# FRONT-UNIT-3_2.net
KiCad netlist of a schematic drawn in Altium Designer
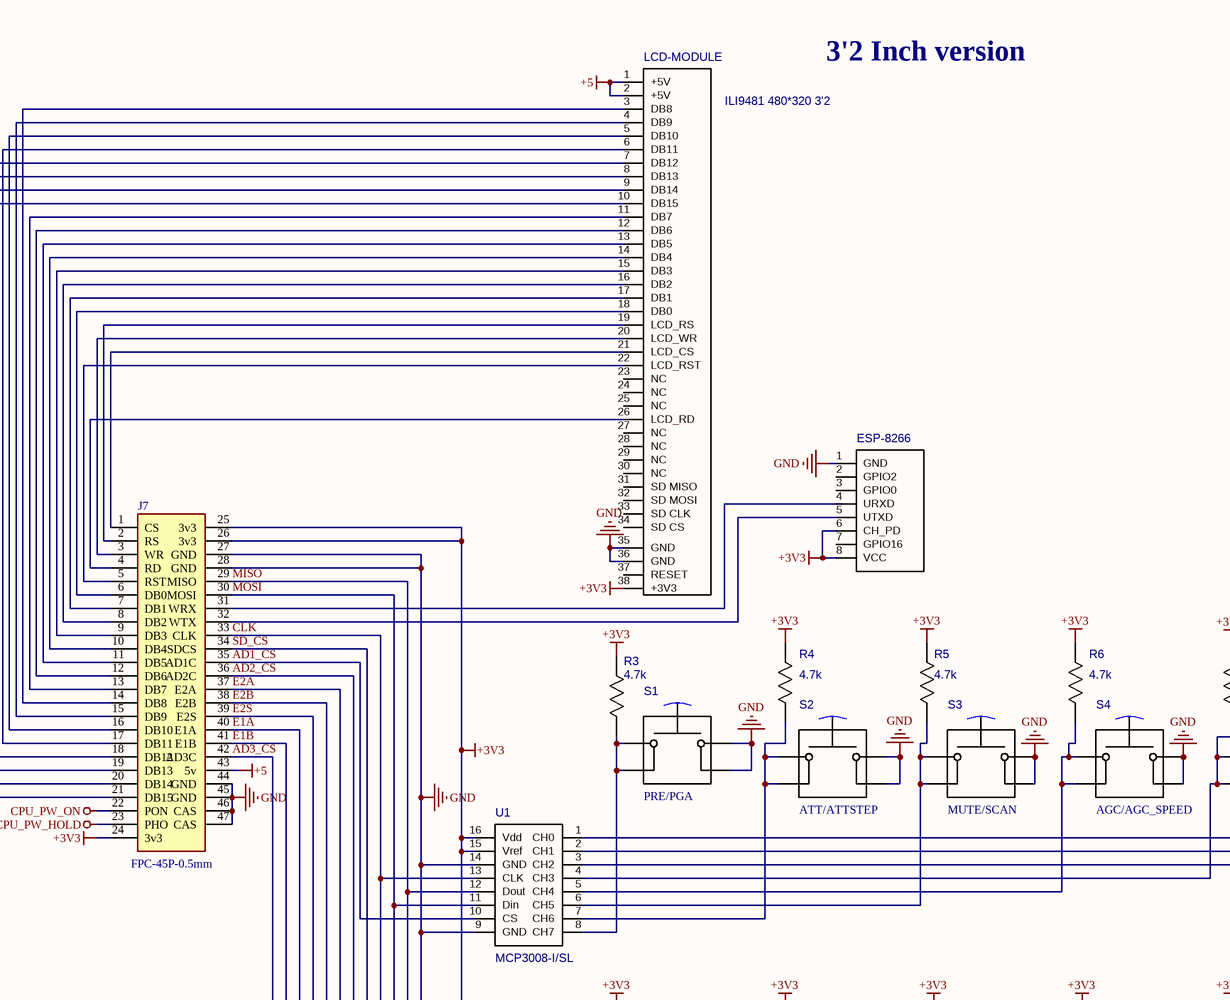
[diagram p0: FRONT-UNIT-3.2.SCHDOC, top left]
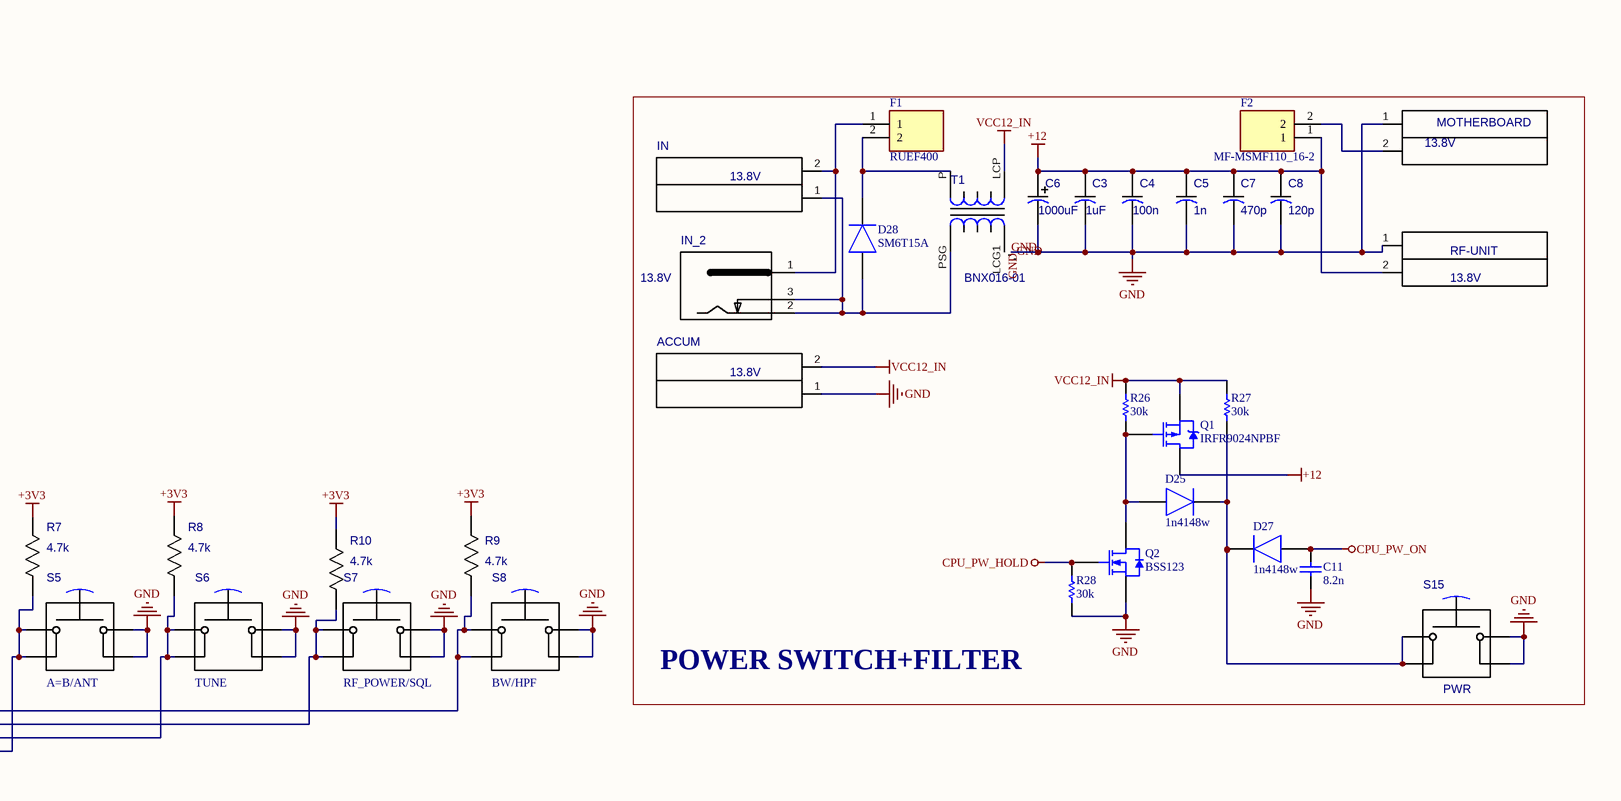
[diagram p1: FRONT-UNIT-3.2.SCHDOC, top right]
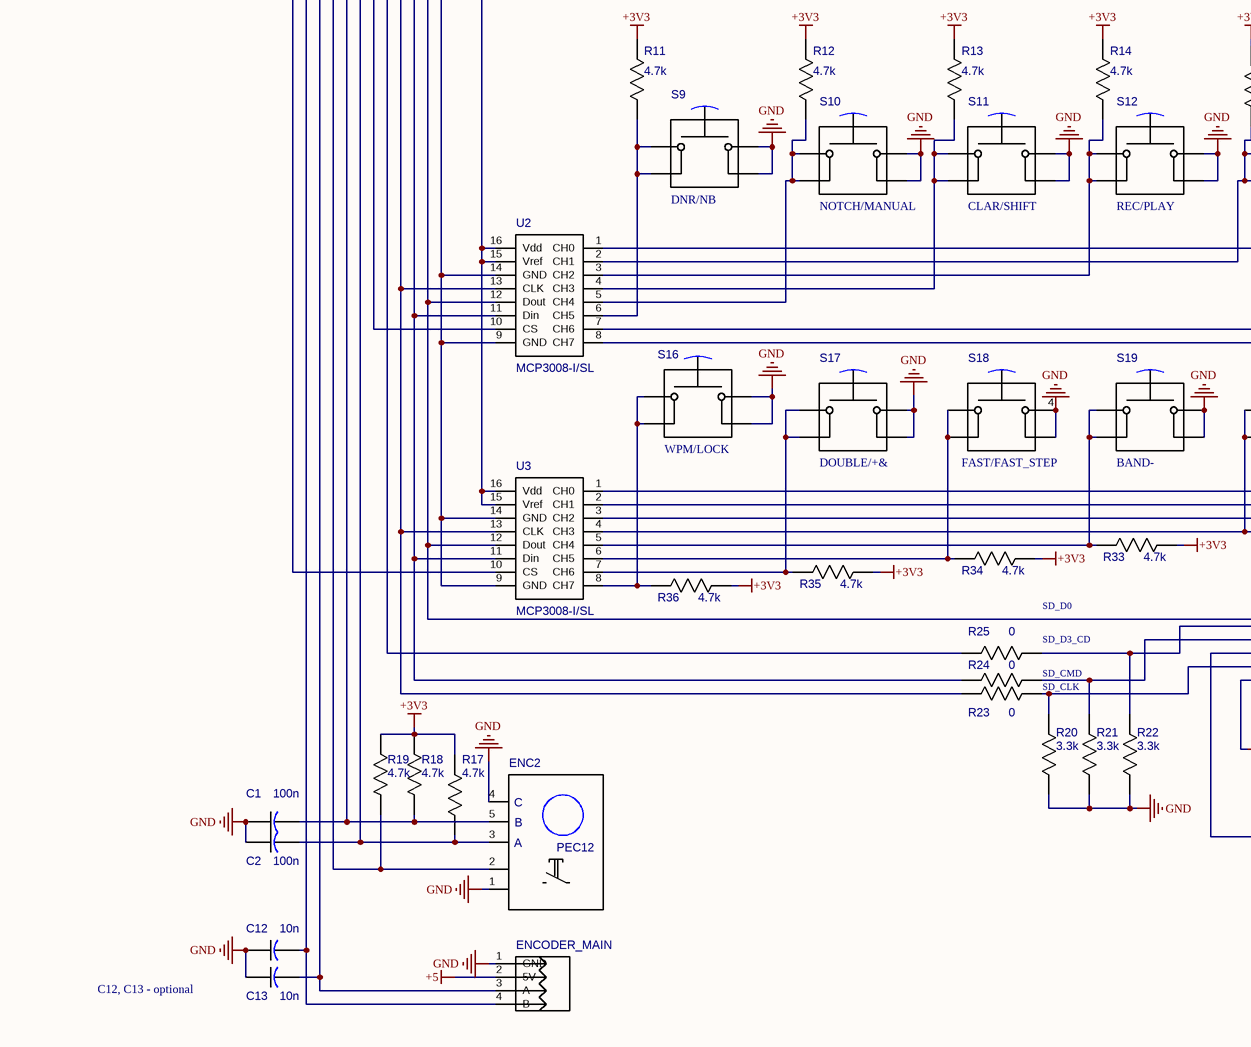
[diagram p2: FRONT-UNIT-3.2.SCHDOC, bottom left]
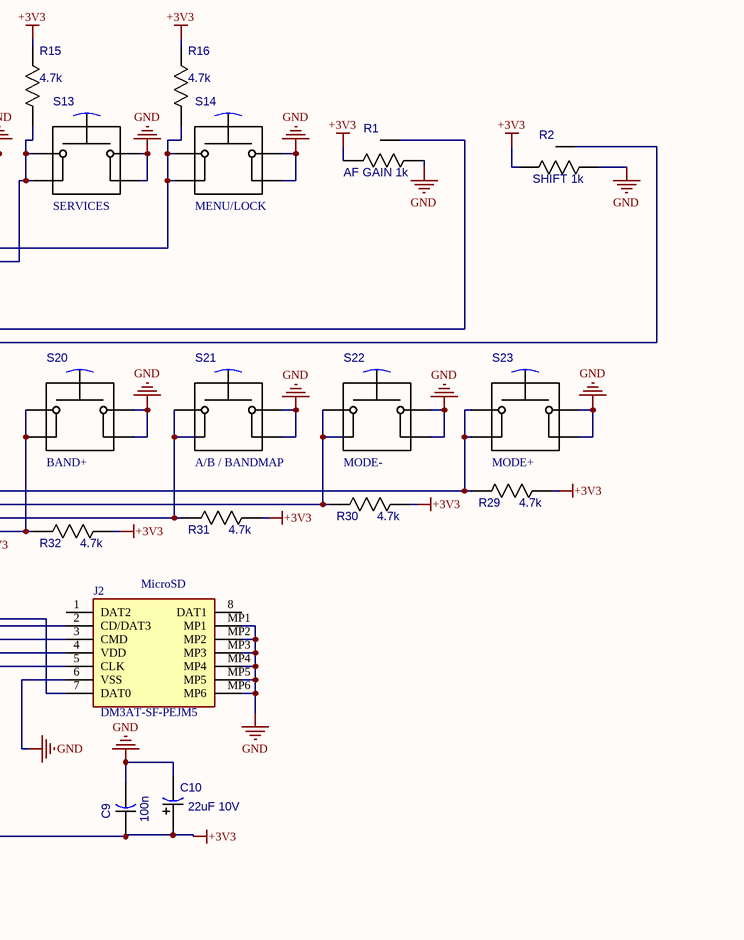
[diagram p3: FRONT-UNIT-3.2.SCHDOC, bottom right]

(export (version "E")
  (design (tool "Eeschema 10.0.6"))
  (components
    (comp (ref "ACCUM")
      (value "13.8V")
      (footprint "JX2")
      (description "JX2")
      (libsource (lib "*") (part "JX2"))
    )
    (comp (ref "C1")
      (value "100n")
      (footprint "CAP_0805")
      (description "CAP_0805")
      (libsource (lib "*") (part "CAP_0805"))
    )
    (comp (ref "C2")
      (value "100n")
      (footprint "CAP_0805")
      (description "CAP_0805")
      (libsource (lib "*") (part "CAP_0805"))
    )
    (comp (ref "C3")
      (value "1uF")
      (footprint "CAP_1206")
      (description "CAP_1206")
      (libsource (lib "*") (part "CAP_1206"))
    )
    (comp (ref "C4")
      (value "100n")
      (footprint "CAP_1206")
      (description "CAP_1206")
      (libsource (lib "*") (part "CAP_1206"))
    )
    (comp (ref "C5")
      (value "1n")
      (footprint "CAP_1206")
      (description "CAP_1206")
      (libsource (lib "*") (part "CAP_1206"))
    )
    (comp (ref "C6")
      (value "1000uF")
      (footprint "CAP250RP")
      (description "CAP250RP")
      (libsource (lib "*") (part "CAP250RP"))
    )
    (comp (ref "C7")
      (value "470p")
      (footprint "CAP_1206")
      (description "CAP_1206")
      (libsource (lib "*") (part "CAP_1206"))
    )
    (comp (ref "C8")
      (value "120p")
      (footprint "CAP_1206")
      (description "CAP_1206")
      (libsource (lib "*") (part "CAP_1206"))
    )
    (comp (ref "C9")
      (value "100n")
      (footprint "CAP_0805")
      (description "CAP_0805")
      (libsource (lib "*") (part "CAP_0805"))
    )
    (comp (ref "C10")
      (value "22uF 10V")
      (footprint "EEEFC_sizeB")
      (description "EEEFC_sizeB")
      (libsource (lib "*") (part "EEEFC_sizeB"))
    )
    (comp (ref "C11")
      (value "8.2n")
      (footprint "CAPC2013X94X50LL20T25")
      (description "CAP_1206")
      (fields
        (field (name "MANUFACTURER") "AVX Interconnect / Elco")
        (field (name "PART NUMBER") "08055C822KAT2A")
      )
      (libsource (lib "Altium Content Vault") (part "CAP"))
    )
    (comp (ref "C12")
      (value "10n")
      (footprint "CAP_0805")
      (description "CAP_0805")
      (libsource (lib "*") (part "CAP_0805"))
    )
    (comp (ref "C13")
      (value "10n")
      (footprint "CAP_0805")
      (description "CAP_0805")
      (libsource (lib "*") (part "CAP_0805"))
    )
    (comp (ref "D25")
      (value "1n4148w")
      (footprint "SamacSys:SOD3716X135N")
      (description "Diode")
      (libsource (lib "*") (part "1n4148w"))
    )
    (comp (ref "D27")
      (value "1n4148w")
      (footprint "SamacSys:SOD3716X135N")
      (description "Diode")
      (libsource (lib "*") (part "1n4148w"))
    )
    (comp (ref "D28")
      (value "SM6T15A")
      (footprint "SamacSys:SMBJ36CATR")
      (description "Diode")
      (fields (field (name "MOUSER PART NUMBER") "511-SM6T15A") (field (name "RS PART NUMBER") "4864915P"))
      (libsource (lib "*") (part "SM6T15A"))
    )
    (comp (ref "ENC2") (value "PEC12") (footprint "PEC12") (libsource (lib "*") (part "PEC12")))
    (comp (ref "ENCODER_MAIN")
      (value "OPTICAL ENCODER")
      (footprint "644456-4")
      (libsource (lib "*") (part "644456-4"))
    )
    (comp (ref "ESP-8266")
      (value "ESP-01 ESP8266")
      (footprint "ESP-01 ESP8266")
      (libsource (lib "*") (part "ESP-01 ESP8266"))
    )
    (comp (ref "F1")
      (value "RUEF400")
      (footprint "SamacSys:RUEF400")
      (description "Fuse")
      (fields (field (name "MOUSER PART NUMBER") "650-RUEF400") (field (name "RS PART NUMBER") "5176837P"))
      (libsource (lib "*") (part "RUEF400"))
    )
    (comp (ref "F2")
      (value "MF-MSMF110_16-2")
      (footprint "SamacSys:FUSC4632X85N")
      (description "Fuse")
      (fields
        (field (name "MANUFACTURER_PART_NUMBER") "MF-MSMF110/16-2")
        (field (name "MOUSER PART NUMBER") "652-MF-MSMF110/16-2")
      )
      (libsource (lib "*") (part "MF-MSMF110_16-2"))
    )
    (comp (ref "IN") (value "13.8V") (footprint "JX2") (description "JX2") (libsource (lib "*") (part "JX2")))
    (comp (ref "IN_2")
      (value "13.8V")
      (footprint "PJ-050B")
      (description "PJ-050B")
      (libsource (lib "*") (part "PJ-050B"))
    )
    (comp (ref "J2")
      (value "DM3AT-SF-PEJM5")
      (footprint "SamacSys:DM3ATSFPEJM5")
      (description "Connector")
      (libsource (lib "*") (part "DM3AT-SF-PEJM5"))
    )
    (comp (ref "J7")
      (value "FPC-45P-0.5mm")
      (footprint "FRONT-UNIT:FH12S45S05SH60")
      (description "Connector")
      (fields
        (field (name "MANUFACTURER_PART_NUMBER") "FH12S-45S-0.5SH(55)")
        (field (name "MOUSER PART NUMBER") "798-FH12S-45S-05SH55")
      )
      (libsource (lib "*") (part "FH12S-45S-0.5SH_55_"))
    )
    (comp (ref "LCD-MODULE")
      (value "ILI9481 480*320 3'2")
      (footprint "LCD-MODULE-3.2-480-320")
      (description "LCD-MODULE_3'2_480х320")
      (libsource (lib "FRONT-UNIT") (part "LCD-MODULE_3'2_480х320"))
    )
    (comp (ref "MOTHERBOARD")
      (value "13.8V")
      (footprint "JX2")
      (description "JX2")
      (libsource (lib "*") (part "JX2"))
    )
    (comp (ref "Q1")
      (value "IRFR9024NPBF")
      (footprint "ONSC-DPAK-3-369C-01_V")
      (description "IRFR9024NPBF, Транзистор, Р-канал 55В 11А")
      (fields (field (name "MANUFACTURER") "On Semiconductor") (field (name "PARTNUMBER") "NTD2955G"))
      (libsource (lib "Altium Content Vault") (part "ONSC-PMOS-G1S3D4-3_B"))
    )
    (comp (ref "Q2")
      (value "BSS123")
      (footprint "FAIR-SOT23-3_V")
      (fields (field (name "MANUFACTURER") "Fairchild"))
      (libsource (lib "Altium Content Vault") (part "NEMOS-GSD-3"))
    )
    (comp (ref "R1")
      (value "AF GAIN 1k")
      (footprint "PTV09")
      (description "Adjustable Resistor PTV09")
      (fields (field (name "Comment") "ptv09a-4225f-b102"))
      (libsource (lib "*") (part "PTV09"))
    )
    (comp (ref "R2")
      (value "SHIFT 1k")
      (footprint "PTV09")
      (description "Adjustable Resistor PTV09")
      (fields (field (name "Comment") "ptv09a-4225f-b102"))
      (libsource (lib "*") (part "PTV09"))
    )
    (comp (ref "R3")
      (value "4.7k")
      (footprint "RES_0805")
      (description "RES_0805")
      (libsource (lib "*") (part "RES_0805"))
    )
    (comp (ref "R4")
      (value "4.7k")
      (footprint "RES_0805")
      (description "RES_0805")
      (libsource (lib "*") (part "RES_0805"))
    )
    (comp (ref "R5")
      (value "4.7k")
      (footprint "RES_0805")
      (description "RES_0805")
      (libsource (lib "*") (part "RES_0805"))
    )
    (comp (ref "R6")
      (value "4.7k")
      (footprint "RES_0805")
      (description "RES_0805")
      (libsource (lib "*") (part "RES_0805"))
    )
    (comp (ref "R7")
      (value "4.7k")
      (footprint "RES_0805")
      (description "RES_0805")
      (libsource (lib "*") (part "RES_0805"))
    )
    (comp (ref "R8")
      (value "4.7k")
      (footprint "RES_0805")
      (description "RES_0805")
      (libsource (lib "*") (part "RES_0805"))
    )
    (comp (ref "R9")
      (value "4.7k")
      (footprint "RES_0805")
      (description "RES_0805")
      (libsource (lib "*") (part "RES_0805"))
    )
    (comp (ref "R10")
      (value "4.7k")
      (footprint "RES_0805")
      (description "RES_0805")
      (libsource (lib "*") (part "RES_0805"))
    )
    (comp (ref "R11")
      (value "4.7k")
      (footprint "RES_0805")
      (description "RES_0805")
      (libsource (lib "*") (part "RES_0805"))
    )
    (comp (ref "R12")
      (value "4.7k")
      (footprint "RES_0805")
      (description "RES_0805")
      (libsource (lib "*") (part "RES_0805"))
    )
    (comp (ref "R13")
      (value "4.7k")
      (footprint "RES_0805")
      (description "RES_0805")
      (libsource (lib "*") (part "RES_0805"))
    )
    (comp (ref "R14")
      (value "4.7k")
      (footprint "RES_0805")
      (description "RES_0805")
      (libsource (lib "*") (part "RES_0805"))
    )
    (comp (ref "R15")
      (value "4.7k")
      (footprint "RES_0805")
      (description "RES_0805")
      (libsource (lib "*") (part "RES_0805"))
    )
    (comp (ref "R16")
      (value "4.7k")
      (footprint "RES_0805")
      (description "RES_0805")
      (libsource (lib "*") (part "RES_0805"))
    )
    (comp (ref "R17")
      (value "4.7k")
      (footprint "RES_0805")
      (description "RES_0805")
      (libsource (lib "*") (part "RES_0805"))
    )
    (comp (ref "R18")
      (value "4.7k")
      (footprint "RES_0805")
      (description "RES_0805")
      (libsource (lib "*") (part "RES_0805"))
    )
    (comp (ref "R19")
      (value "4.7k")
      (footprint "RES_0805")
      (description "RES_0805")
      (libsource (lib "*") (part "RES_0805"))
    )
    (comp (ref "R20")
      (value "3.3k")
      (footprint "RES_0805")
      (description "RES_0805")
      (libsource (lib "*") (part "RES_0805"))
    )
    (comp (ref "R21")
      (value "3.3k")
      (footprint "RES_0805")
      (description "RES_0805")
      (libsource (lib "*") (part "RES_0805"))
    )
    (comp (ref "R22")
      (value "3.3k")
      (footprint "RES_0805")
      (description "RES_0805")
      (libsource (lib "*") (part "RES_0805"))
    )
    (comp (ref "R23")
      (value "0")
      (footprint "RES_0805")
      (description "RES_0805")
      (libsource (lib "*") (part "RES_0805"))
    )
    (comp (ref "R24")
      (value "0")
      (footprint "RES_0805")
      (description "RES_0805")
      (libsource (lib "*") (part "RES_0805"))
    )
    (comp (ref "R25")
      (value "0")
      (footprint "RES_0805")
      (description "RES_0805")
      (libsource (lib "*") (part "RES_0805"))
    )
    (comp (ref "R26")
      (value "30k")
      (footprint "RESC2013X60X40NL20T25")
      (description "RES_0805")
      (fields (field (name "MANUFACTURER") "Panasonic") (field (name "PART NUMBER") "ERA-6AEB303V"))
      (libsource (lib "Altium Content Vault") (part "RES"))
    )
    (comp (ref "R27")
      (value "30k")
      (footprint "RESC2013X60X40NL20T25")
      (description "RES_0805")
      (fields (field (name "MANUFACTURER") "Panasonic") (field (name "PART NUMBER") "ERA-6AEB303V"))
      (libsource (lib "Altium Content Vault") (part "RES"))
    )
    (comp (ref "R28")
      (value "30k")
      (footprint "RESC2013X60X40NL20T25")
      (description "RES_0805")
      (fields (field (name "MANUFACTURER") "Panasonic") (field (name "PART NUMBER") "ERA-6AEB303V"))
      (libsource (lib "Altium Content Vault") (part "RES"))
    )
    (comp (ref "R29")
      (value "4.7k")
      (footprint "RES_0805")
      (description "RES_0805")
      (libsource (lib "*") (part "RES_0805"))
    )
    (comp (ref "R30")
      (value "4.7k")
      (footprint "RES_0805")
      (description "RES_0805")
      (libsource (lib "*") (part "RES_0805"))
    )
    (comp (ref "R31")
      (value "4.7k")
      (footprint "RES_0805")
      (description "RES_0805")
      (libsource (lib "*") (part "RES_0805"))
    )
    (comp (ref "R32")
      (value "4.7k")
      (footprint "RES_0805")
      (description "RES_0805")
      (libsource (lib "*") (part "RES_0805"))
    )
    (comp (ref "R33")
      (value "4.7k")
      (footprint "RES_0805")
      (description "RES_0805")
      (libsource (lib "*") (part "RES_0805"))
    )
    (comp (ref "R34")
      (value "4.7k")
      (footprint "RES_0805")
      (description "RES_0805")
      (libsource (lib "*") (part "RES_0805"))
    )
    (comp (ref "R35")
      (value "4.7k")
      (footprint "RES_0805")
      (description "RES_0805")
      (libsource (lib "*") (part "RES_0805"))
    )
    (comp (ref "R36")
      (value "4.7k")
      (footprint "RES_0805")
      (description "RES_0805")
      (libsource (lib "*") (part "RES_0805"))
    )
    (comp (ref "RF-UNIT")
      (value "13.8V")
      (footprint "JX2")
      (description "JX2")
      (libsource (lib "*") (part "JX2"))
    )
    (comp (ref "S1")
      (value "PTS645SK50LFS")
      (footprint "PTS645SK50LFS")
      (fields (field (name "LCSC PART #") "test"))
      (libsource (lib "*") (part "PTS645SK50LFS"))
    )
    (comp (ref "S2")
      (value "PTS645SK50LFS")
      (footprint "PTS645SK50LFS")
      (libsource (lib "*") (part "PTS645SK50LFS"))
    )
    (comp (ref "S3")
      (value "PTS645SK50LFS")
      (footprint "PTS645SK50LFS")
      (libsource (lib "*") (part "PTS645SK50LFS"))
    )
    (comp (ref "S4")
      (value "PTS645SK50LFS")
      (footprint "PTS645SK50LFS")
      (libsource (lib "*") (part "PTS645SK50LFS"))
    )
    (comp (ref "S5")
      (value "PTS645SK50LFS")
      (footprint "PTS645SK50LFS")
      (libsource (lib "*") (part "PTS645SK50LFS"))
    )
    (comp (ref "S6")
      (value "PTS645SK50LFS")
      (footprint "PTS645SK50LFS")
      (libsource (lib "*") (part "PTS645SK50LFS"))
    )
    (comp (ref "S7")
      (value "PTS645SK50LFS")
      (footprint "PTS645SK50LFS")
      (libsource (lib "*") (part "PTS645SK50LFS"))
    )
    (comp (ref "S8")
      (value "PTS645SK50LFS")
      (footprint "PTS645SK50LFS")
      (libsource (lib "*") (part "PTS645SK50LFS"))
    )
    (comp (ref "S9")
      (value "PTS645SK50LFS")
      (footprint "PTS645SK50LFS")
      (libsource (lib "*") (part "PTS645SK50LFS"))
    )
    (comp (ref "S10")
      (value "PTS645SK50LFS")
      (footprint "PTS645SK50LFS")
      (libsource (lib "*") (part "PTS645SK50LFS"))
    )
    (comp (ref "S11")
      (value "PTS645SK50LFS")
      (footprint "PTS645SK50LFS")
      (libsource (lib "*") (part "PTS645SK50LFS"))
    )
    (comp (ref "S12")
      (value "PTS645SK50LFS")
      (footprint "PTS645SK50LFS")
      (libsource (lib "*") (part "PTS645SK50LFS"))
    )
    (comp (ref "S13")
      (value "PTS645SK50LFS")
      (footprint "PTS645SK50LFS")
      (libsource (lib "*") (part "PTS645SK50LFS"))
    )
    (comp (ref "S14")
      (value "PTS645SK50LFS")
      (footprint "PTS645SK50LFS")
      (libsource (lib "*") (part "PTS645SK50LFS"))
    )
    (comp (ref "S15")
      (value "PWR")
      (footprint "PTS645SK50LFS")
      (description "PTS645SK50LFS")
      (libsource (lib "*") (part "PTS645SK50LFS"))
    )
    (comp (ref "S16")
      (value "PTS645SK50LFS")
      (footprint "PTS645SK50LFS")
      (libsource (lib "*") (part "PTS645SK50LFS"))
    )
    (comp (ref "S17")
      (value "PTS645SK50LFS")
      (footprint "PTS645SK50LFS")
      (libsource (lib "*") (part "PTS645SK50LFS"))
    )
    (comp (ref "S18")
      (value "PTS645SK50LFS")
      (footprint "PTS645SK50LFS")
      (libsource (lib "") (part "PTS645SK50LFS_1"))
    )
    (comp (ref "S19")
      (value "PTS645SK50LFS")
      (footprint "PTS645SK50LFS")
      (libsource (lib "*") (part "PTS645SK50LFS"))
    )
    (comp (ref "S20")
      (value "PTS645SK50LFS")
      (footprint "PTS645SK50LFS")
      (libsource (lib "*") (part "PTS645SK50LFS"))
    )
    (comp (ref "S21")
      (value "PTS645SK50LFS")
      (footprint "PTS645SK50LFS")
      (libsource (lib "*") (part "PTS645SK50LFS"))
    )
    (comp (ref "S22")
      (value "PTS645SK50LFS")
      (footprint "PTS645SK50LFS")
      (libsource (lib "*") (part "PTS645SK50LFS"))
    )
    (comp (ref "S23")
      (value "PTS645SK50LFS")
      (footprint "PTS645SK50LFS")
      (libsource (lib "*") (part "PTS645SK50LFS"))
    )
    (comp (ref "T1")
      (value "BNX016-01")
      (footprint "TRANSF_ICORE")
      (libsource (lib "*") (part "TRANSF_ICORE"))
    )
    (comp (ref "U1")
      (value "MCP3008-I/SL")
      (footprint "MCP3008-I/SL")
      (libsource (lib "*") (part "MCP3008-I/SL"))
    )
    (comp (ref "U2")
      (value "MCP3008-I/SL")
      (footprint "MCP3008-I/SL")
      (libsource (lib "*") (part "MCP3008-I/SL"))
    )
    (comp (ref "U3")
      (value "MCP3008-I/SL")
      (footprint "MCP3008-I/SL")
      (libsource (lib "*") (part "MCP3008-I/SL"))
    )
  )
  (nets
    (net (code "1") (name "+3V3") (class "Default")
      (node (ref "C10") (pin "1") (pinfunction "PLUS_1") (pintype "passive"))
      (node (ref "C9") (pin "1") (pinfunction "1_1") (pintype "passive"))
      (node (ref "ESP-8266") (pin "6") (pinfunction "CH_PD_6") (pintype "passive"))
      (node (ref "ESP-8266") (pin "8") (pinfunction "VCC_8") (pintype "passive"))
      (node (ref "J2") (pin "4") (pinfunction "VDD_4") (pintype "passive"))
      (node (ref "J7") (pin "24") (pinfunction "3v3_24") (pintype "passive"))
      (node (ref "J7") (pin "25") (pinfunction "3v3_25") (pintype "passive"))
      (node (ref "J7") (pin "26") (pinfunction "3v3_26") (pintype "passive"))
      (node (ref "LCD-MODULE") (pin "38") (pinfunction "+3V3_38") (pintype "passive"))
      (node (ref "R1") (pin "1") (pinfunction "CW_1") (pintype "passive"))
      (node (ref "R10") (pin "2") (pinfunction "2_2") (pintype "passive"))
      (node (ref "R11") (pin "2") (pinfunction "2_2") (pintype "passive"))
      (node (ref "R12") (pin "2") (pinfunction "2_2") (pintype "passive"))
      (node (ref "R13") (pin "2") (pinfunction "2_2") (pintype "passive"))
      (node (ref "R14") (pin "2") (pinfunction "2_2") (pintype "passive"))
      (node (ref "R15") (pin "2") (pinfunction "2_2") (pintype "passive"))
      (node (ref "R16") (pin "2") (pinfunction "2_2") (pintype "passive"))
      (node (ref "R17") (pin "2") (pinfunction "2_2") (pintype "passive"))
      (node (ref "R18") (pin "2") (pinfunction "2_2") (pintype "passive"))
      (node (ref "R19") (pin "2") (pinfunction "2_2") (pintype "passive"))
      (node (ref "R2") (pin "1") (pinfunction "CW_1") (pintype "passive"))
      (node (ref "R29") (pin "2") (pinfunction "2_2") (pintype "passive"))
      (node (ref "R3") (pin "2") (pinfunction "2_2") (pintype "passive"))
      (node (ref "R30") (pin "2") (pinfunction "2_2") (pintype "passive"))
      (node (ref "R31") (pin "2") (pinfunction "2_2") (pintype "passive"))
      (node (ref "R32") (pin "2") (pinfunction "2_2") (pintype "passive"))
      (node (ref "R33") (pin "2") (pinfunction "2_2") (pintype "passive"))
      (node (ref "R34") (pin "2") (pinfunction "2_2") (pintype "passive"))
      (node (ref "R35") (pin "2") (pinfunction "2_2") (pintype "passive"))
      (node (ref "R36") (pin "2") (pinfunction "2_2") (pintype "passive"))
      (node (ref "R4") (pin "2") (pinfunction "2_2") (pintype "passive"))
      (node (ref "R5") (pin "2") (pinfunction "2_2") (pintype "passive"))
      (node (ref "R6") (pin "2") (pinfunction "2_2") (pintype "passive"))
      (node (ref "R7") (pin "2") (pinfunction "2_2") (pintype "passive"))
      (node (ref "R8") (pin "2") (pinfunction "2_2") (pintype "passive"))
      (node (ref "R9") (pin "2") (pinfunction "2_2") (pintype "passive"))
      (node (ref "U1") (pin "15") (pinfunction "Vref_15") (pintype "passive"))
      (node (ref "U1") (pin "16") (pinfunction "Vdd_16") (pintype "passive"))
      (node (ref "U2") (pin "15") (pinfunction "Vref_15") (pintype "passive"))
      (node (ref "U2") (pin "16") (pinfunction "Vdd_16") (pintype "passive"))
      (node (ref "U3") (pin "15") (pinfunction "Vref_15") (pintype "passive"))
      (node (ref "U3") (pin "16") (pinfunction "Vdd_16") (pintype "passive"))
    )
    (net (code "2") (name "+5") (class "Default")
      (node (ref "ENCODER_MAIN") (pin "2") (pinfunction "5V_2") (pintype "passive"))
      (node (ref "J7") (pin "43") (pinfunction "5v_43") (pintype "passive"))
      (node (ref "LCD-MODULE") (pin "1") (pinfunction "+5V_1") (pintype "passive"))
      (node (ref "LCD-MODULE") (pin "2") (pinfunction "+5V_2") (pintype "passive"))
    )
    (net (code "3") (name "+12") (class "Default")
      (node (ref "C3") (pin "1") (pinfunction "1_1") (pintype "passive"))
      (node (ref "C4") (pin "1") (pinfunction "1_1") (pintype "passive"))
      (node (ref "C5") (pin "1") (pinfunction "1_1") (pintype "passive"))
      (node (ref "C6") (pin "1") (pinfunction "PLUS_1") (pintype "passive"))
      (node (ref "C7") (pin "1") (pinfunction "1_1") (pintype "passive"))
      (node (ref "C8") (pin "1") (pinfunction "1_1") (pintype "passive"))
      (node (ref "F2") (pin "1") (pinfunction "1_1") (pintype "passive"))
      (node (ref "Q1") (pin "4") (pinfunction "D_4") (pintype "passive"))
      (node (ref "RF-UNIT") (pin "2") (pinfunction "1_2") (pintype "passive"))
    )
    (net (code "4") (name "/AD1_CS") (class "Default")
      (node (ref "J7") (pin "35") (pinfunction "AD1C_35") (pintype "passive"))
      (node (ref "U1") (pin "10") (pinfunction "CS_10") (pintype "passive"))
    )
    (net (code "5") (name "/AD2_CS") (class "Default")
      (node (ref "J7") (pin "36") (pinfunction "AD2C_36") (pintype "passive"))
      (node (ref "U2") (pin "10") (pinfunction "CS_10") (pintype "passive"))
    )
    (net (code "6") (name "/AD3_CS") (class "Default")
      (node (ref "J7") (pin "42") (pinfunction "AD3C_42") (pintype "passive"))
      (node (ref "U3") (pin "10") (pinfunction "CS_10") (pintype "passive"))
    )
    (net (code "7") (name "/CLK") (class "Default")
      (node (ref "J7") (pin "33") (pinfunction "CLK_33") (pintype "passive"))
      (node (ref "R23") (pin "2") (pinfunction "2_2") (pintype "passive"))
      (node (ref "U1") (pin "13") (pinfunction "CLK_13") (pintype "passive"))
      (node (ref "U2") (pin "13") (pinfunction "CLK_13") (pintype "passive"))
      (node (ref "U3") (pin "13") (pinfunction "CLK_13") (pintype "passive"))
    )
    (net (code "8") (name "/E1A") (class "Default")
      (node (ref "C13") (pin "2") (pinfunction "2_2") (pintype "passive"))
      (node (ref "ENCODER_MAIN") (pin "3") (pinfunction "A_3") (pintype "passive"))
      (node (ref "J7") (pin "40") (pinfunction "E1A_40") (pintype "passive"))
    )
    (net (code "9") (name "/E1B") (class "Default")
      (node (ref "C12") (pin "2") (pinfunction "2_2") (pintype "passive"))
      (node (ref "ENCODER_MAIN") (pin "4") (pinfunction "B_4") (pintype "passive"))
      (node (ref "J7") (pin "41") (pinfunction "E1B_41") (pintype "passive"))
    )
    (net (code "10") (name "/E2A") (class "Default")
      (node (ref "C2") (pin "2") (pinfunction "2_2") (pintype "passive"))
      (node (ref "ENC2") (pin "3") (pinfunction "A_3") (pintype "passive"))
      (node (ref "J7") (pin "37") (pinfunction "E2A_37") (pintype "passive"))
      (node (ref "R17") (pin "1") (pinfunction "1_1") (pintype "passive"))
    )
    (net (code "11") (name "/E2B") (class "Default")
      (node (ref "C1") (pin "2") (pinfunction "2_2") (pintype "passive"))
      (node (ref "ENC2") (pin "5") (pinfunction "B_5") (pintype "passive"))
      (node (ref "J7") (pin "38") (pinfunction "E2B_38") (pintype "passive"))
      (node (ref "R18") (pin "1") (pinfunction "1_1") (pintype "passive"))
    )
    (net (code "12") (name "/E2S") (class "Default")
      (node (ref "ENC2") (pin "2") (pinfunction "2_2") (pintype "passive"))
      (node (ref "J7") (pin "39") (pinfunction "E2S_39") (pintype "passive"))
      (node (ref "R19") (pin "1") (pinfunction "1_1") (pintype "passive"))
    )
    (net (code "13") (name "/MISO") (class "Default")
      (node (ref "J2") (pin "7") (pinfunction "DAT0_7") (pintype "passive"))
      (node (ref "J7") (pin "29") (pinfunction "MISO_29") (pintype "passive"))
      (node (ref "U1") (pin "12") (pinfunction "Dout_12") (pintype "passive"))
      (node (ref "U2") (pin "12") (pinfunction "Dout_12") (pintype "passive"))
      (node (ref "U3") (pin "12") (pinfunction "Dout_12") (pintype "passive"))
    )
    (net (code "14") (name "/MOSI") (class "Default")
      (node (ref "J7") (pin "30") (pinfunction "MOSI_30") (pintype "passive"))
      (node (ref "R24") (pin "2") (pinfunction "2_2") (pintype "passive"))
      (node (ref "U1") (pin "11") (pinfunction "Din_11") (pintype "passive"))
      (node (ref "U2") (pin "11") (pinfunction "Din_11") (pintype "passive"))
      (node (ref "U3") (pin "11") (pinfunction "Din_11") (pintype "passive"))
    )
    (net (code "15") (name "/SD_CS") (class "Default")
      (node (ref "J7") (pin "34") (pinfunction "SDCS_34") (pintype "passive"))
      (node (ref "R25") (pin "2") (pinfunction "2_2") (pintype "passive"))
    )
    (net (code "16") (name "CPU_PW_HOLD") (class "Default")
      (node (ref "J7") (pin "23") (pinfunction "PHO_23") (pintype "passive"))
      (node (ref "Q2") (pin "1") (pinfunction "G_1") (pintype "passive"))
      (node (ref "R28") (pin "2") (pinfunction "2_2") (pintype "passive"))
    )
    (net (code "17") (name "CPU_PW_ON") (class "Default")
      (node (ref "C11") (pin "2") (pinfunction "2_2") (pintype "passive"))
      (node (ref "D27") (pin "2") (pinfunction "A_2") (pintype "passive"))
      (node (ref "J7") (pin "22") (pinfunction "PON_22") (pintype "passive"))
    )
    (net (code "18") (name "GND") (class "Default")
      (node (ref "ACCUM") (pin "1") (pinfunction "2_1") (pintype "passive"))
      (node (ref "C1") (pin "1") (pinfunction "1_1") (pintype "passive"))
      (node (ref "C10") (pin "2") (pinfunction "MINUS_2") (pintype "passive"))
      (node (ref "C11") (pin "1") (pinfunction "1_1") (pintype "passive"))
      (node (ref "C12") (pin "1") (pinfunction "1_1") (pintype "passive"))
      (node (ref "C13") (pin "1") (pinfunction "1_1") (pintype "passive"))
      (node (ref "C2") (pin "1") (pinfunction "1_1") (pintype "passive"))
      (node (ref "C3") (pin "2") (pinfunction "2_2") (pintype "passive"))
      (node (ref "C4") (pin "2") (pinfunction "2_2") (pintype "passive"))
      (node (ref "C5") (pin "2") (pinfunction "2_2") (pintype "passive"))
      (node (ref "C6") (pin "2") (pinfunction "MINUS_2") (pintype "passive"))
      (node (ref "C7") (pin "2") (pinfunction "2_2") (pintype "passive"))
      (node (ref "C8") (pin "2") (pinfunction "2_2") (pintype "passive"))
      (node (ref "C9") (pin "2") (pinfunction "2_2") (pintype "passive"))
      (node (ref "ENC2") (pin "1") (pinfunction "1_1") (pintype "passive"))
      (node (ref "ENC2") (pin "4") (pinfunction "C_4") (pintype "passive"))
      (node (ref "ENCODER_MAIN") (pin "1") (pinfunction "GND_1") (pintype "passive"))
      (node (ref "ESP-8266") (pin "1") (pinfunction "GND_1") (pintype "passive"))
      (node (ref "J2") (pin "6") (pinfunction "VSS_6") (pintype "passive"))
      (node (ref "J2") (pin "MP1") (pinfunction "MP1_MP1") (pintype "passive"))
      (node (ref "J2") (pin "MP2") (pinfunction "MP2_MP2") (pintype "passive"))
      (node (ref "J2") (pin "MP3") (pinfunction "MP3_MP3") (pintype "passive"))
      (node (ref "J2") (pin "MP4") (pinfunction "MP4_MP4") (pintype "passive"))
      (node (ref "J2") (pin "MP5") (pinfunction "MP5_MP5") (pintype "passive"))
      (node (ref "J2") (pin "MP6") (pinfunction "MP6_MP6") (pintype "passive"))
      (node (ref "J7") (pin "27") (pinfunction "GND_27") (pintype "passive"))
      (node (ref "J7") (pin "28") (pinfunction "GND_28") (pintype "passive"))
      (node (ref "J7") (pin "44") (pinfunction "GND_44") (pintype "passive"))
      (node (ref "J7") (pin "45") (pinfunction "GND_45") (pintype "passive"))
      (node (ref "J7") (pin "46") (pinfunction "CAS_46") (pintype "passive"))
      (node (ref "J7") (pin "47") (pinfunction "CAS_47") (pintype "passive"))
      (node (ref "LCD-MODULE") (pin "35") (pinfunction "GND_35") (pintype "passive"))
      (node (ref "LCD-MODULE") (pin "36") (pinfunction "GND_36") (pintype "passive"))
      (node (ref "MOTHERBOARD") (pin "1") (pinfunction "2_1") (pintype "passive"))
      (node (ref "Q2") (pin "2") (pinfunction "S_2") (pintype "passive"))
      (node (ref "R1") (pin "3") (pinfunction "CCW_3") (pintype "passive"))
      (node (ref "R2") (pin "3") (pinfunction "CCW_3") (pintype "passive"))
      (node (ref "R20") (pin "1") (pinfunction "1_1") (pintype "passive"))
      (node (ref "R21") (pin "1") (pinfunction "1_1") (pintype "passive"))
      (node (ref "R22") (pin "1") (pinfunction "1_1") (pintype "passive"))
      (node (ref "R28") (pin "1") (pinfunction "1_1") (pintype "passive"))
      (node (ref "RF-UNIT") (pin "1") (pinfunction "2_1") (pintype "passive"))
      (node (ref "S1") (pin "3") (pinfunction "B_3") (pintype "passive"))
      (node (ref "S1") (pin "4") (pinfunction "B_4") (pintype "passive"))
      (node (ref "S10") (pin "3") (pinfunction "B_3") (pintype "passive"))
      (node (ref "S10") (pin "4") (pinfunction "B_4") (pintype "passive"))
      (node (ref "S11") (pin "3") (pinfunction "B_3") (pintype "passive"))
      (node (ref "S11") (pin "4") (pinfunction "B_4") (pintype "passive"))
      (node (ref "S12") (pin "3") (pinfunction "B_3") (pintype "passive"))
      (node (ref "S12") (pin "4") (pinfunction "B_4") (pintype "passive"))
      (node (ref "S13") (pin "3") (pinfunction "B_3") (pintype "passive"))
      (node (ref "S13") (pin "4") (pinfunction "B_4") (pintype "passive"))
      (node (ref "S14") (pin "3") (pinfunction "B_3") (pintype "passive"))
      (node (ref "S14") (pin "4") (pinfunction "B_4") (pintype "passive"))
      (node (ref "S15") (pin "3") (pinfunction "B_3") (pintype "passive"))
      (node (ref "S15") (pin "4") (pinfunction "B_4") (pintype "passive"))
      (node (ref "S16") (pin "3") (pinfunction "B_3") (pintype "passive"))
      (node (ref "S16") (pin "4") (pinfunction "B_4") (pintype "passive"))
      (node (ref "S17") (pin "3") (pinfunction "B_3") (pintype "passive"))
      (node (ref "S17") (pin "4") (pinfunction "B_4") (pintype "passive"))
      (node (ref "S18") (pin "3") (pinfunction "B_3") (pintype "passive"))
      (node (ref "S18") (pin "4") (pinfunction "B_4") (pintype "passive"))
      (node (ref "S19") (pin "3") (pinfunction "B_3") (pintype "passive"))
      (node (ref "S19") (pin "4") (pinfunction "B_4") (pintype "passive"))
      (node (ref "S2") (pin "3") (pinfunction "B_3") (pintype "passive"))
      (node (ref "S2") (pin "4") (pinfunction "B_4") (pintype "passive"))
      (node (ref "S20") (pin "3") (pinfunction "B_3") (pintype "passive"))
      (node (ref "S20") (pin "4") (pinfunction "B_4") (pintype "passive"))
      (node (ref "S21") (pin "3") (pinfunction "B_3") (pintype "passive"))
      (node (ref "S21") (pin "4") (pinfunction "B_4") (pintype "passive"))
      (node (ref "S22") (pin "3") (pinfunction "B_3") (pintype "passive"))
      (node (ref "S22") (pin "4") (pinfunction "B_4") (pintype "passive"))
      (node (ref "S23") (pin "3") (pinfunction "B_3") (pintype "passive"))
      (node (ref "S23") (pin "4") (pinfunction "B_4") (pintype "passive"))
      (node (ref "S3") (pin "3") (pinfunction "B_3") (pintype "passive"))
      (node (ref "S3") (pin "4") (pinfunction "B_4") (pintype "passive"))
      (node (ref "S4") (pin "3") (pinfunction "B_3") (pintype "passive"))
      (node (ref "S4") (pin "4") (pinfunction "B_4") (pintype "passive"))
      (node (ref "S5") (pin "3") (pinfunction "B_3") (pintype "passive"))
      (node (ref "S5") (pin "4") (pinfunction "B_4") (pintype "passive"))
      (node (ref "S6") (pin "3") (pinfunction "B_3") (pintype "passive"))
      (node (ref "S6") (pin "4") (pinfunction "B_4") (pintype "passive"))
      (node (ref "S7") (pin "3") (pinfunction "B_3") (pintype "passive"))
      (node (ref "S7") (pin "4") (pinfunction "B_4") (pintype "passive"))
      (node (ref "S8") (pin "3") (pinfunction "B_3") (pintype "passive"))
      (node (ref "S8") (pin "4") (pinfunction "B_4") (pintype "passive"))
      (node (ref "S9") (pin "3") (pinfunction "B_3") (pintype "passive"))
      (node (ref "S9") (pin "4") (pinfunction "B_4") (pintype "passive"))
      (node (ref "T1") (pin "LCG1") (pinfunction "S2_LCG1") (pintype "passive"))
      (node (ref "T1") (pin "LCG2") (pinfunction "0_LCG2") (pintype "passive"))
      (node (ref "T1") (pin "LCG3") (pinfunction "0_LCG3") (pintype "passive"))
      (node (ref "U1") (pin "14") (pinfunction "GND_14") (pintype "passive"))
      (node (ref "U1") (pin "9") (pinfunction "GND_9") (pintype "passive"))
      (node (ref "U2") (pin "14") (pinfunction "GND_14") (pintype "passive"))
      (node (ref "U2") (pin "9") (pinfunction "GND_9") (pintype "passive"))
      (node (ref "U3") (pin "14") (pinfunction "GND_14") (pintype "passive"))
      (node (ref "U3") (pin "9") (pinfunction "GND_9") (pintype "passive"))
    )
    (net (code "19") (name "Net-(D25-A)") (class "Default")
      (node (ref "D25") (pin "2") (pinfunction "A_2") (pintype "passive"))
      (node (ref "Q1") (pin "1") (pinfunction "G_1") (pintype "passive"))
      (node (ref "Q2") (pin "3") (pinfunction "D_3") (pintype "passive"))
      (node (ref "R26") (pin "1") (pinfunction "1_1") (pintype "passive"))
    )
    (net (code "20") (name "Net-(D25-K)") (class "Default")
      (node (ref "D25") (pin "1") (pinfunction "K_1") (pintype "passive"))
      (node (ref "D27") (pin "1") (pinfunction "K_1") (pintype "passive"))
      (node (ref "R27") (pin "1") (pinfunction "1_1") (pintype "passive"))
      (node (ref "S15") (pin "1") (pinfunction "A_1") (pintype "passive"))
      (node (ref "S15") (pin "2") (pinfunction "A_2") (pintype "passive"))
    )
    (net (code "21") (name "Net-(D28-A)") (class "Default")
      (node (ref "D28") (pin "2") (pinfunction "A_2") (pintype "passive"))
      (node (ref "IN") (pin "1") (pinfunction "2_1") (pintype "passive"))
      (node (ref "IN_2") (pin "2") (pinfunction "2_2") (pintype "passive"))
      (node (ref "IN_2") (pin "3") (pinfunction "3_3") (pintype "passive"))
      (node (ref "T1") (pin "PSG") (pinfunction "S1_PSG") (pintype "passive"))
    )
    (net (code "22") (name "Net-(D28-K)") (class "Default")
      (node (ref "D28") (pin "1") (pinfunction "K_1") (pintype "passive"))
      (node (ref "F1") (pin "2") (pinfunction "2_2") (pintype "passive"))
      (node (ref "T1") (pin "P") (pinfunction "P1_P") (pintype "passive"))
    )
    (net (code "23") (name "Net-(ESP-8266-URXD)") (class "Default")
      (node (ref "ESP-8266") (pin "4") (pinfunction "URXD_4") (pintype "passive"))
      (node (ref "J7") (pin "31") (pinfunction "WRX_31") (pintype "passive"))
    )
    (net (code "24") (name "Net-(ESP-8266-UTXD)") (class "Default")
      (node (ref "ESP-8266") (pin "5") (pinfunction "UTXD_5") (pintype "passive"))
      (node (ref "J7") (pin "32") (pinfunction "WTX_32") (pintype "passive"))
    )
    (net (code "25") (name "Net-(IN-1)") (class "Default")
      (node (ref "F1") (pin "1") (pinfunction "1_1") (pintype "passive"))
      (node (ref "IN") (pin "2") (pinfunction "1_2") (pintype "passive"))
      (node (ref "IN_2") (pin "1") (pinfunction "1_1") (pintype "passive"))
    )
    (net (code "26") (name "Net-(J2-CD{slash}DAT3)") (class "Default")
      (node (ref "J2") (pin "2") (pinfunction "CD/DAT3_2") (pintype "passive"))
      (node (ref "R22") (pin "2") (pinfunction "2_2") (pintype "passive"))
      (node (ref "R25") (pin "1") (pinfunction "1_1") (pintype "passive"))
    )
    (net (code "27") (name "Net-(J2-CLK)") (class "Default")
      (node (ref "J2") (pin "5") (pinfunction "CLK_5") (pintype "passive"))
      (node (ref "R20") (pin "2") (pinfunction "2_2") (pintype "passive"))
      (node (ref "R23") (pin "1") (pinfunction "1_1") (pintype "passive"))
    )
    (net (code "28") (name "Net-(J2-CMD)") (class "Default")
      (node (ref "J2") (pin "3") (pinfunction "CMD_3") (pintype "passive"))
      (node (ref "R21") (pin "2") (pinfunction "2_2") (pintype "passive"))
      (node (ref "R24") (pin "1") (pinfunction "1_1") (pintype "passive"))
    )
    (net (code "29") (name "Net-(J7-CS)") (class "Default")
      (node (ref "J7") (pin "1") (pinfunction "CS_1") (pintype "passive"))
      (node (ref "LCD-MODULE") (pin "21") (pinfunction "LCD_CS_21") (pintype "passive"))
    )
    (net (code "30") (name "Net-(J7-DB0)") (class "Default")
      (node (ref "J7") (pin "6") (pinfunction "DB0_6") (pintype "passive"))
      (node (ref "LCD-MODULE") (pin "18") (pinfunction "DB0_18") (pintype "passive"))
    )
    (net (code "31") (name "Net-(J7-DB1)") (class "Default")
      (node (ref "J7") (pin "7") (pinfunction "DB1_7") (pintype "passive"))
      (node (ref "LCD-MODULE") (pin "17") (pinfunction "DB1_17") (pintype "passive"))
    )
    (net (code "32") (name "Net-(J7-DB2)") (class "Default")
      (node (ref "J7") (pin "8") (pinfunction "DB2_8") (pintype "passive"))
      (node (ref "LCD-MODULE") (pin "16") (pinfunction "DB2_16") (pintype "passive"))
    )
    (net (code "33") (name "Net-(J7-DB3)") (class "Default")
      (node (ref "J7") (pin "9") (pinfunction "DB3_9") (pintype "passive"))
      (node (ref "LCD-MODULE") (pin "15") (pinfunction "DB3_15") (pintype "passive"))
    )
    (net (code "34") (name "Net-(J7-DB4)") (class "Default")
      (node (ref "J7") (pin "10") (pinfunction "DB4_10") (pintype "passive"))
      (node (ref "LCD-MODULE") (pin "14") (pinfunction "DB4_14") (pintype "passive"))
    )
    (net (code "35") (name "Net-(J7-DB5)") (class "Default")
      (node (ref "J7") (pin "11") (pinfunction "DB5_11") (pintype "passive"))
      (node (ref "LCD-MODULE") (pin "13") (pinfunction "DB5_13") (pintype "passive"))
    )
    (net (code "36") (name "Net-(J7-DB6)") (class "Default")
      (node (ref "J7") (pin "12") (pinfunction "DB6_12") (pintype "passive"))
      (node (ref "LCD-MODULE") (pin "12") (pinfunction "DB6_12") (pintype "passive"))
    )
    (net (code "37") (name "Net-(J7-DB7)") (class "Default")
      (node (ref "J7") (pin "13") (pinfunction "DB7_13") (pintype "passive"))
      (node (ref "LCD-MODULE") (pin "11") (pinfunction "DB7_11") (pintype "passive"))
    )
    (net (code "38") (name "Net-(J7-DB8)") (class "Default")
      (node (ref "J7") (pin "14") (pinfunction "DB8_14") (pintype "passive"))
      (node (ref "LCD-MODULE") (pin "3") (pinfunction "DB8_3") (pintype "passive"))
    )
    (net (code "39") (name "Net-(J7-DB9)") (class "Default")
      (node (ref "J7") (pin "15") (pinfunction "DB9_15") (pintype "passive"))
      (node (ref "LCD-MODULE") (pin "4") (pinfunction "DB9_4") (pintype "passive"))
    )
    (net (code "40") (name "Net-(J7-DB10)") (class "Default")
      (node (ref "J7") (pin "16") (pinfunction "DB10_16") (pintype "passive"))
      (node (ref "LCD-MODULE") (pin "5") (pinfunction "DB10_5") (pintype "passive"))
    )
    (net (code "41") (name "Net-(J7-DB11)") (class "Default")
      (node (ref "J7") (pin "17") (pinfunction "DB11_17") (pintype "passive"))
      (node (ref "LCD-MODULE") (pin "6") (pinfunction "DB11_6") (pintype "passive"))
    )
    (net (code "42") (name "Net-(J7-DB12)") (class "Default")
      (node (ref "J7") (pin "18") (pinfunction "DB12_18") (pintype "passive"))
      (node (ref "LCD-MODULE") (pin "7") (pinfunction "DB12_7") (pintype "passive"))
    )
    (net (code "43") (name "Net-(J7-DB13)") (class "Default")
      (node (ref "J7") (pin "19") (pinfunction "DB13_19") (pintype "passive"))
      (node (ref "LCD-MODULE") (pin "8") (pinfunction "DB13_8") (pintype "passive"))
    )
    (net (code "44") (name "Net-(J7-DB14)") (class "Default")
      (node (ref "J7") (pin "20") (pinfunction "DB14_20") (pintype "passive"))
      (node (ref "LCD-MODULE") (pin "9") (pinfunction "DB14_9") (pintype "passive"))
    )
    (net (code "45") (name "Net-(J7-DB15)") (class "Default")
      (node (ref "J7") (pin "21") (pinfunction "DB15_21") (pintype "passive"))
      (node (ref "LCD-MODULE") (pin "10") (pinfunction "DB15_10") (pintype "passive"))
    )
    (net (code "46") (name "Net-(J7-RD)") (class "Default")
      (node (ref "J7") (pin "4") (pinfunction "RD_4") (pintype "passive"))
      (node (ref "LCD-MODULE") (pin "26") (pinfunction "LCD_RD_26") (pintype "passive"))
    )
    (net (code "47") (name "Net-(J7-RS)") (class "Default")
      (node (ref "J7") (pin "2") (pinfunction "RS_2") (pintype "passive"))
      (node (ref "LCD-MODULE") (pin "19") (pinfunction "LCD_RS_19") (pintype "passive"))
    )
    (net (code "48") (name "Net-(J7-RST)") (class "Default")
      (node (ref "J7") (pin "5") (pinfunction "RST_5") (pintype "passive"))
      (node (ref "LCD-MODULE") (pin "22") (pinfunction "LCD_RST_22") (pintype "passive"))
    )
    (net (code "49") (name "Net-(J7-WR)") (class "Default")
      (node (ref "J7") (pin "3") (pinfunction "WR_3") (pintype "passive"))
      (node (ref "LCD-MODULE") (pin "20") (pinfunction "LCD_WR_20") (pintype "passive"))
    )
    (net (code "50") (name "Net-(MOTHERBOARD-1)") (class "Default")
      (node (ref "F2") (pin "2") (pinfunction "2_2") (pintype "passive"))
      (node (ref "MOTHERBOARD") (pin "2") (pinfunction "1_2") (pintype "passive"))
    )
    (net (code "51") (name "Net-(R1-W)") (class "Default")
      (node (ref "R1") (pin "2") (pinfunction "W_2") (pintype "passive"))
      (node (ref "U2") (pin "7") (pinfunction "CH6_7") (pintype "passive"))
    )
    (net (code "52") (name "Net-(R2-W)") (class "Default")
      (node (ref "R2") (pin "2") (pinfunction "W_2") (pintype "passive"))
      (node (ref "U2") (pin "8") (pinfunction "CH7_8") (pintype "passive"))
    )
    (net (code "53") (name "Net-(U1-CH0)") (class "Default")
      (node (ref "R9") (pin "1") (pinfunction "1_1") (pintype "passive"))
      (node (ref "S8") (pin "1") (pinfunction "A_1") (pintype "passive"))
      (node (ref "S8") (pin "2") (pinfunction "A_2") (pintype "passive"))
      (node (ref "U1") (pin "1") (pinfunction "CH0_1") (pintype "passive"))
    )
    (net (code "54") (name "Net-(U1-CH1)") (class "Default")
      (node (ref "R10") (pin "1") (pinfunction "1_1") (pintype "passive"))
      (node (ref "S7") (pin "1") (pinfunction "A_1") (pintype "passive"))
      (node (ref "S7") (pin "2") (pinfunction "A_2") (pintype "passive"))
      (node (ref "U1") (pin "2") (pinfunction "CH1_2") (pintype "passive"))
    )
    (net (code "55") (name "Net-(U1-CH2)") (class "Default")
      (node (ref "R8") (pin "1") (pinfunction "1_1") (pintype "passive"))
      (node (ref "S6") (pin "1") (pinfunction "A_1") (pintype "passive"))
      (node (ref "S6") (pin "2") (pinfunction "A_2") (pintype "passive"))
      (node (ref "U1") (pin "3") (pinfunction "CH2_3") (pintype "passive"))
    )
    (net (code "56") (name "Net-(U1-CH3)") (class "Default")
      (node (ref "R7") (pin "1") (pinfunction "1_1") (pintype "passive"))
      (node (ref "S5") (pin "1") (pinfunction "A_1") (pintype "passive"))
      (node (ref "S5") (pin "2") (pinfunction "A_2") (pintype "passive"))
      (node (ref "U1") (pin "4") (pinfunction "CH3_4") (pintype "passive"))
    )
    (net (code "57") (name "Net-(U1-CH4)") (class "Default")
      (node (ref "R6") (pin "1") (pinfunction "1_1") (pintype "passive"))
      (node (ref "S4") (pin "1") (pinfunction "A_1") (pintype "passive"))
      (node (ref "S4") (pin "2") (pinfunction "A_2") (pintype "passive"))
      (node (ref "U1") (pin "5") (pinfunction "CH4_5") (pintype "passive"))
    )
    (net (code "58") (name "Net-(U1-CH5)") (class "Default")
      (node (ref "R5") (pin "1") (pinfunction "1_1") (pintype "passive"))
      (node (ref "S3") (pin "1") (pinfunction "A_1") (pintype "passive"))
      (node (ref "S3") (pin "2") (pinfunction "A_2") (pintype "passive"))
      (node (ref "U1") (pin "6") (pinfunction "CH5_6") (pintype "passive"))
    )
    (net (code "59") (name "Net-(U1-CH6)") (class "Default")
      (node (ref "R4") (pin "1") (pinfunction "1_1") (pintype "passive"))
      (node (ref "S2") (pin "1") (pinfunction "A_1") (pintype "passive"))
      (node (ref "S2") (pin "2") (pinfunction "A_2") (pintype "passive"))
      (node (ref "U1") (pin "7") (pinfunction "CH6_7") (pintype "passive"))
    )
    (net (code "60") (name "Net-(U1-CH7)") (class "Default")
      (node (ref "R3") (pin "1") (pinfunction "1_1") (pintype "passive"))
      (node (ref "S1") (pin "1") (pinfunction "A_1") (pintype "passive"))
      (node (ref "S1") (pin "2") (pinfunction "A_2") (pintype "passive"))
      (node (ref "U1") (pin "8") (pinfunction "CH7_8") (pintype "passive"))
    )
    (net (code "61") (name "Net-(U2-CH0)") (class "Default")
      (node (ref "R16") (pin "1") (pinfunction "1_1") (pintype "passive"))
      (node (ref "S14") (pin "1") (pinfunction "A_1") (pintype "passive"))
      (node (ref "S14") (pin "2") (pinfunction "A_2") (pintype "passive"))
      (node (ref "U2") (pin "1") (pinfunction "CH0_1") (pintype "passive"))
    )
    (net (code "62") (name "Net-(U2-CH1)") (class "Default")
      (node (ref "R15") (pin "1") (pinfunction "1_1") (pintype "passive"))
      (node (ref "S13") (pin "1") (pinfunction "A_1") (pintype "passive"))
      (node (ref "S13") (pin "2") (pinfunction "A_2") (pintype "passive"))
      (node (ref "U2") (pin "2") (pinfunction "CH1_2") (pintype "passive"))
    )
    (net (code "63") (name "Net-(U2-CH2)") (class "Default")
      (node (ref "R14") (pin "1") (pinfunction "1_1") (pintype "passive"))
      (node (ref "S12") (pin "1") (pinfunction "A_1") (pintype "passive"))
      (node (ref "S12") (pin "2") (pinfunction "A_2") (pintype "passive"))
      (node (ref "U2") (pin "3") (pinfunction "CH2_3") (pintype "passive"))
    )
    (net (code "64") (name "Net-(U2-CH3)") (class "Default")
      (node (ref "R13") (pin "1") (pinfunction "1_1") (pintype "passive"))
      (node (ref "S11") (pin "1") (pinfunction "A_1") (pintype "passive"))
      (node (ref "S11") (pin "2") (pinfunction "A_2") (pintype "passive"))
      (node (ref "U2") (pin "4") (pinfunction "CH3_4") (pintype "passive"))
    )
    (net (code "65") (name "Net-(U2-CH4)") (class "Default")
      (node (ref "R12") (pin "1") (pinfunction "1_1") (pintype "passive"))
      (node (ref "S10") (pin "1") (pinfunction "A_1") (pintype "passive"))
      (node (ref "S10") (pin "2") (pinfunction "A_2") (pintype "passive"))
      (node (ref "U2") (pin "5") (pinfunction "CH4_5") (pintype "passive"))
    )
    (net (code "66") (name "Net-(U2-CH5)") (class "Default")
      (node (ref "R11") (pin "1") (pinfunction "1_1") (pintype "passive"))
      (node (ref "S9") (pin "1") (pinfunction "A_1") (pintype "passive"))
      (node (ref "S9") (pin "2") (pinfunction "A_2") (pintype "passive"))
      (node (ref "U2") (pin "6") (pinfunction "CH5_6") (pintype "passive"))
    )
    (net (code "67") (name "Net-(U3-CH0)") (class "Default")
      (node (ref "R29") (pin "1") (pinfunction "1_1") (pintype "passive"))
      (node (ref "S23") (pin "1") (pinfunction "A_1") (pintype "passive"))
      (node (ref "S23") (pin "2") (pinfunction "A_2") (pintype "passive"))
      (node (ref "U3") (pin "1") (pinfunction "CH0_1") (pintype "passive"))
    )
    (net (code "68") (name "Net-(U3-CH1)") (class "Default")
      (node (ref "R30") (pin "1") (pinfunction "1_1") (pintype "passive"))
      (node (ref "S22") (pin "1") (pinfunction "A_1") (pintype "passive"))
      (node (ref "S22") (pin "2") (pinfunction "A_2") (pintype "passive"))
      (node (ref "U3") (pin "2") (pinfunction "CH1_2") (pintype "passive"))
    )
    (net (code "69") (name "Net-(U3-CH2)") (class "Default")
      (node (ref "R31") (pin "1") (pinfunction "1_1") (pintype "passive"))
      (node (ref "S21") (pin "1") (pinfunction "A_1") (pintype "passive"))
      (node (ref "S21") (pin "2") (pinfunction "A_2") (pintype "passive"))
      (node (ref "U3") (pin "3") (pinfunction "CH2_3") (pintype "passive"))
    )
    (net (code "70") (name "Net-(U3-CH3)") (class "Default")
      (node (ref "R32") (pin "1") (pinfunction "1_1") (pintype "passive"))
      (node (ref "S20") (pin "1") (pinfunction "A_1") (pintype "passive"))
      (node (ref "S20") (pin "2") (pinfunction "A_2") (pintype "passive"))
      (node (ref "U3") (pin "4") (pinfunction "CH3_4") (pintype "passive"))
    )
    (net (code "71") (name "Net-(U3-CH4)") (class "Default")
      (node (ref "R33") (pin "1") (pinfunction "1_1") (pintype "passive"))
      (node (ref "S19") (pin "1") (pinfunction "A_1") (pintype "passive"))
      (node (ref "S19") (pin "2") (pinfunction "A_2") (pintype "passive"))
      (node (ref "U3") (pin "5") (pinfunction "CH4_5") (pintype "passive"))
    )
    (net (code "72") (name "Net-(U3-CH5)") (class "Default")
      (node (ref "R34") (pin "1") (pinfunction "1_1") (pintype "passive"))
      (node (ref "S18") (pin "1") (pinfunction "A_1") (pintype "passive"))
      (node (ref "S18") (pin "2") (pinfunction "A_2") (pintype "passive"))
      (node (ref "U3") (pin "6") (pinfunction "CH5_6") (pintype "passive"))
    )
    (net (code "73") (name "Net-(U3-CH6)") (class "Default")
      (node (ref "R35") (pin "1") (pinfunction "1_1") (pintype "passive"))
      (node (ref "S17") (pin "1") (pinfunction "A_1") (pintype "passive"))
      (node (ref "S17") (pin "2") (pinfunction "A_2") (pintype "passive"))
      (node (ref "U3") (pin "7") (pinfunction "CH6_7") (pintype "passive"))
    )
    (net (code "74") (name "Net-(U3-CH7)") (class "Default")
      (node (ref "R36") (pin "1") (pinfunction "1_1") (pintype "passive"))
      (node (ref "S16") (pin "1") (pinfunction "A_1") (pintype "passive"))
      (node (ref "S16") (pin "2") (pinfunction "A_2") (pintype "passive"))
      (node (ref "U3") (pin "8") (pinfunction "CH7_8") (pintype "passive"))
    )
    (net (code "75") (name "VCC12_IN") (class "Default")
      (node (ref "ACCUM") (pin "2") (pinfunction "1_2") (pintype "passive"))
      (node (ref "Q1") (pin "3") (pinfunction "S_3") (pintype "passive"))
      (node (ref "R26") (pin "2") (pinfunction "2_2") (pintype "passive"))
      (node (ref "R27") (pin "2") (pinfunction "2_2") (pintype "passive"))
      (node (ref "T1") (pin "LCP") (pinfunction "P2_LCP") (pintype "passive"))
    )
    (net (code "76") (name "unconnected-(ESP-8266-GPIO0-Pad3)") (class "Default")
      (node (ref "ESP-8266") (pin "3") (pinfunction "GPIO0_3") (pintype "passive"))
    )
    (net (code "77") (name "unconnected-(ESP-8266-GPIO2-Pad2)") (class "Default")
      (node (ref "ESP-8266") (pin "2") (pinfunction "GPIO2_2") (pintype "passive"))
    )
    (net (code "78") (name "unconnected-(ESP-8266-GPIO16-Pad7)") (class "Default")
      (node (ref "ESP-8266") (pin "7") (pinfunction "GPIO16_7") (pintype "passive"))
    )
    (net (code "79") (name "unconnected-(J2-DAT1-Pad8)") (class "Default")
      (node (ref "J2") (pin "8") (pinfunction "DAT1_8") (pintype "passive"))
    )
    (net (code "80") (name "unconnected-(J2-DAT2-Pad1)") (class "Default")
      (node (ref "J2") (pin "1") (pinfunction "DAT2_1") (pintype "passive"))
    )
    (net (code "81") (name "unconnected-(LCD-MODULE-NC-Pad23)") (class "Default")
      (node (ref "LCD-MODULE") (pin "23") (pinfunction "NC_23") (pintype "passive"))
    )
    (net (code "82") (name "unconnected-(LCD-MODULE-NC-Pad24)") (class "Default")
      (node (ref "LCD-MODULE") (pin "24") (pinfunction "NC_24") (pintype "passive"))
    )
    (net (code "83") (name "unconnected-(LCD-MODULE-NC-Pad25)") (class "Default")
      (node (ref "LCD-MODULE") (pin "25") (pinfunction "NC_25") (pintype "passive"))
    )
    (net (code "84") (name "unconnected-(LCD-MODULE-NC-Pad27)") (class "Default")
      (node (ref "LCD-MODULE") (pin "27") (pinfunction "NC_27") (pintype "passive"))
    )
    (net (code "85") (name "unconnected-(LCD-MODULE-NC-Pad28)") (class "Default")
      (node (ref "LCD-MODULE") (pin "28") (pinfunction "NC_28") (pintype "passive"))
    )
    (net (code "86") (name "unconnected-(LCD-MODULE-NC-Pad29)") (class "Default")
      (node (ref "LCD-MODULE") (pin "29") (pinfunction "NC_29") (pintype "passive"))
    )
    (net (code "87") (name "unconnected-(LCD-MODULE-NC-Pad30)") (class "Default")
      (node (ref "LCD-MODULE") (pin "30") (pinfunction "NC_30") (pintype "passive"))
    )
    (net (code "88") (name "unconnected-(LCD-MODULE-RESET-Pad37)") (class "Default")
      (node (ref "LCD-MODULE") (pin "37") (pinfunction "RESET_37") (pintype "passive"))
    )
    (net (code "89") (name "unconnected-(LCD-MODULE-SD_CLK-Pad33)") (class "Default")
      (node (ref "LCD-MODULE") (pin "33") (pinfunction "SD_CLK_33") (pintype "passive"))
    )
    (net (code "90") (name "unconnected-(LCD-MODULE-SD_CS-Pad34)") (class "Default")
      (node (ref "LCD-MODULE") (pin "34") (pinfunction "SD_CS_34") (pintype "passive"))
    )
    (net (code "91") (name "unconnected-(LCD-MODULE-SD_MISO-Pad31)") (class "Default")
      (node (ref "LCD-MODULE") (pin "31") (pinfunction "SD_MISO_31") (pintype "passive"))
    )
    (net (code "92") (name "unconnected-(LCD-MODULE-SD_MOSI-Pad32)") (class "Default")
      (node (ref "LCD-MODULE") (pin "32") (pinfunction "SD_MOSI_32") (pintype "passive"))
    )
  )
)
